# AS_Node_Inputs.net
KiCad netlist of a schematic drawn in Altium Designer
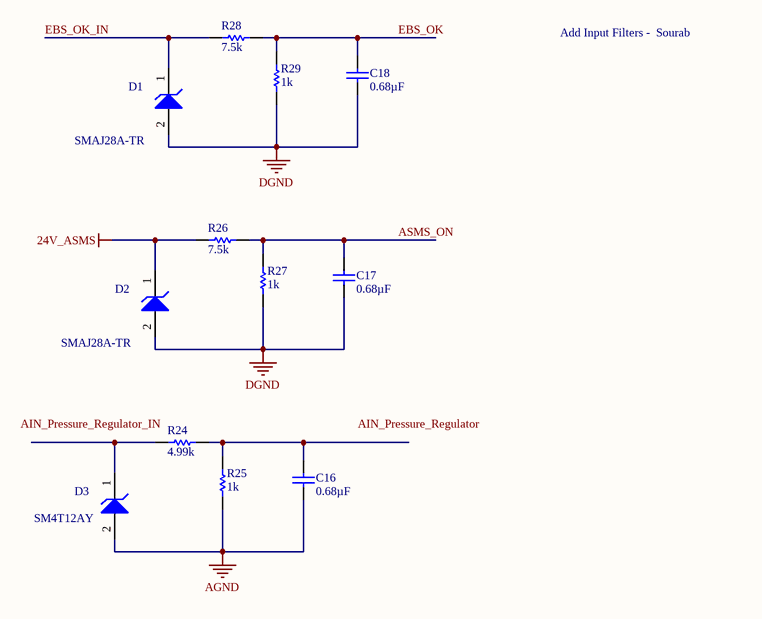
[diagram p0: AS_Node_Inputs.SchDoc]

(export (version "E")
  (design (tool "Eeschema 10.0.6"))
  (components
    (comp (ref "C16")
      (value "0.68µF")
      (footprint "dV_C0805")
      (fields
        (field (name "MANUFACTURER") "KEMET")
        (field (name "MANUFACTURER PART NUMBER") "C0805C684J3NACTU")
      )
      (libsource (lib "altium-import") (part "root_1_Cap_"))
    )
    (comp (ref "C17")
      (value "0.68µF")
      (footprint "dV_C0805")
      (fields
        (field (name "MANUFACTURER") "KEMET")
        (field (name "MANUFACTURER PART NUMBER") "C0805C684J3NACTU")
      )
      (libsource (lib "altium-import") (part "root_1_Cap_"))
    )
    (comp (ref "C18")
      (value "0.68µF")
      (footprint "dV_C0805")
      (fields
        (field (name "MANUFACTURER") "KEMET")
        (field (name "MANUFACTURER PART NUMBER") "C0805C684J3NACTU")
      )
      (libsource (lib "altium-import") (part "root_1_Cap_"))
    )
    (comp (ref "D1")
      (value "~")
      (footprint "1SMA12AT3G")
      (fields
        (field (name "MANUFACTURER") "STMICROELECTRONICS")
        (field (name "MANUFACTURER PART NUMBER") "SMAJ28A-TR")
      )
      (libsource (lib "altium-import") (part "root_3_TVS diodes_"))
    )
    (comp (ref "D2")
      (value "~")
      (footprint "1SMA12AT3G")
      (fields
        (field (name "MANUFACTURER") "STMICROELECTRONICS")
        (field (name "MANUFACTURER PART NUMBER") "SMAJ28A-TR")
      )
      (libsource (lib "altium-import") (part "root_3_TVS diodes_"))
    )
    (comp (ref "D3")
      (value "~")
      (footprint "1SMA12AT3G")
      (fields
        (field (name "MANUFACTURER") "STMICROELECTRONICS")
        (field (name "MANUFACTURER PART NUMBER") "SM4T12AY")
      )
      (libsource (lib "altium-import") (part "root_3_TVS diodes_"))
    )
    (comp (ref "R24")
      (value "4.99k")
      (footprint "dV_R0805")
      (fields
        (field (name "MANUFACTURER") "PANASONIC ELECTRONIC COMPONENTS")
        (field (name "MANUFACTURER PART NUMBER") "ERA6AEB4991V")
      )
      (libsource (lib "altium-import") (part "root_2_Res1_"))
    )
    (comp (ref "R25")
      (value "1k")
      (footprint "dV_R0805")
      (fields
        (field (name "MANUFACTURER") "PANASONIC ELECTRONIC COMPONENTS")
        (field (name "MANUFACTURER PART NUMBER") "ERA6AEB102V")
      )
      (libsource (lib "altium-import") (part "root_3_Res1_"))
    )
    (comp (ref "R26")
      (value "7.5k")
      (footprint "dV_R0805")
      (fields
        (field (name "MANUFACTURER") "PANASONIC ELECTRONIC COMPONENTS")
        (field (name "MANUFACTURER PART NUMBER") "ERA6AEB752V")
      )
      (libsource (lib "altium-import") (part "root_2_Res1_"))
    )
    (comp (ref "R27")
      (value "1k")
      (footprint "dV_R0805")
      (fields
        (field (name "MANUFACTURER") "PANASONIC ELECTRONIC COMPONENTS")
        (field (name "MANUFACTURER PART NUMBER") "ERA6AEB102V")
      )
      (libsource (lib "altium-import") (part "root_3_Res1_"))
    )
    (comp (ref "R28")
      (value "7.5k")
      (footprint "dV_R0805")
      (fields
        (field (name "MANUFACTURER") "PANASONIC ELECTRONIC COMPONENTS")
        (field (name "MANUFACTURER PART NUMBER") "ERA6AEB752V")
      )
      (libsource (lib "altium-import") (part "root_2_Res1_"))
    )
    (comp (ref "R29")
      (value "1k")
      (footprint "dV_R0805")
      (fields
        (field (name "MANUFACTURER") "PANASONIC ELECTRONIC COMPONENTS")
        (field (name "MANUFACTURER PART NUMBER") "ERA6AEB102V")
      )
      (libsource (lib "altium-import") (part "root_3_Res1_"))
    )
  )
  (nets
    (net (code "3") (name "/ASMS_ON") (class "Default")
      (node (ref "C17") (pin "2") (pinfunction "2_2") (pintype "passive"))
      (node (ref "R26") (pin "1") (pinfunction "1_1") (pintype "passive"))
      (node (ref "R27") (pin "1") (pinfunction "1_1") (pintype "passive"))
    )
    (net (code "4") (name "/EBS_OK") (class "Default")
      (node (ref "C18") (pin "2") (pinfunction "2_2") (pintype "passive"))
      (node (ref "R28") (pin "1") (pinfunction "1_1") (pintype "passive"))
      (node (ref "R29") (pin "1") (pinfunction "1_1") (pintype "passive"))
    )
    (net (code "5") (name "/EBS_OK_IN") (class "Default")
      (node (ref "D1") (pin "1") (pinfunction "K_1") (pintype "passive"))
      (node (ref "R28") (pin "2") (pinfunction "2_2") (pintype "passive"))
    )
    (net (code "6") (name "24V_ASMS") (class "Default")
      (node (ref "D2") (pin "1") (pinfunction "K_1") (pintype "passive"))
      (node (ref "R26") (pin "2") (pinfunction "2_2") (pintype "passive"))
    )
    (net (code "7") (name "AGND") (class "Default")
      (node (ref "C16") (pin "1") (pinfunction "1_1") (pintype "passive"))
      (node (ref "D3") (pin "2") (pinfunction "A_2") (pintype "passive"))
      (node (ref "R25") (pin "2") (pinfunction "2_2") (pintype "passive"))
    )
    (net (code "8") (name "DGND") (class "Default")
      (node (ref "C17") (pin "1") (pinfunction "1_1") (pintype "passive"))
      (node (ref "C18") (pin "1") (pinfunction "1_1") (pintype "passive"))
      (node (ref "D1") (pin "2") (pinfunction "A_2") (pintype "passive"))
      (node (ref "D2") (pin "2") (pinfunction "A_2") (pintype "passive"))
      (node (ref "R27") (pin "2") (pinfunction "2_2") (pintype "passive"))
      (node (ref "R29") (pin "2") (pinfunction "2_2") (pintype "passive"))
    )
    (net (code "9") (name "Net-(C16-Pad2)") (class "Default")
      (node (ref "C16") (pin "2") (pinfunction "2_2") (pintype "passive"))
      (node (ref "R24") (pin "1") (pinfunction "1_1") (pintype "passive"))
      (node (ref "R25") (pin "1") (pinfunction "1_1") (pintype "passive"))
    )
    (net (code "10") (name "Net-(D3-K)") (class "Default")
      (node (ref "D3") (pin "1") (pinfunction "K_1") (pintype "passive"))
      (node (ref "R24") (pin "2") (pinfunction "2_2") (pintype "passive"))
    )
  )
)
